# Hank2.net
KiCad netlist of a schematic drawn in EAGLE
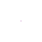
[diagram p0: schematic, sheet 1, part 1 of 2]
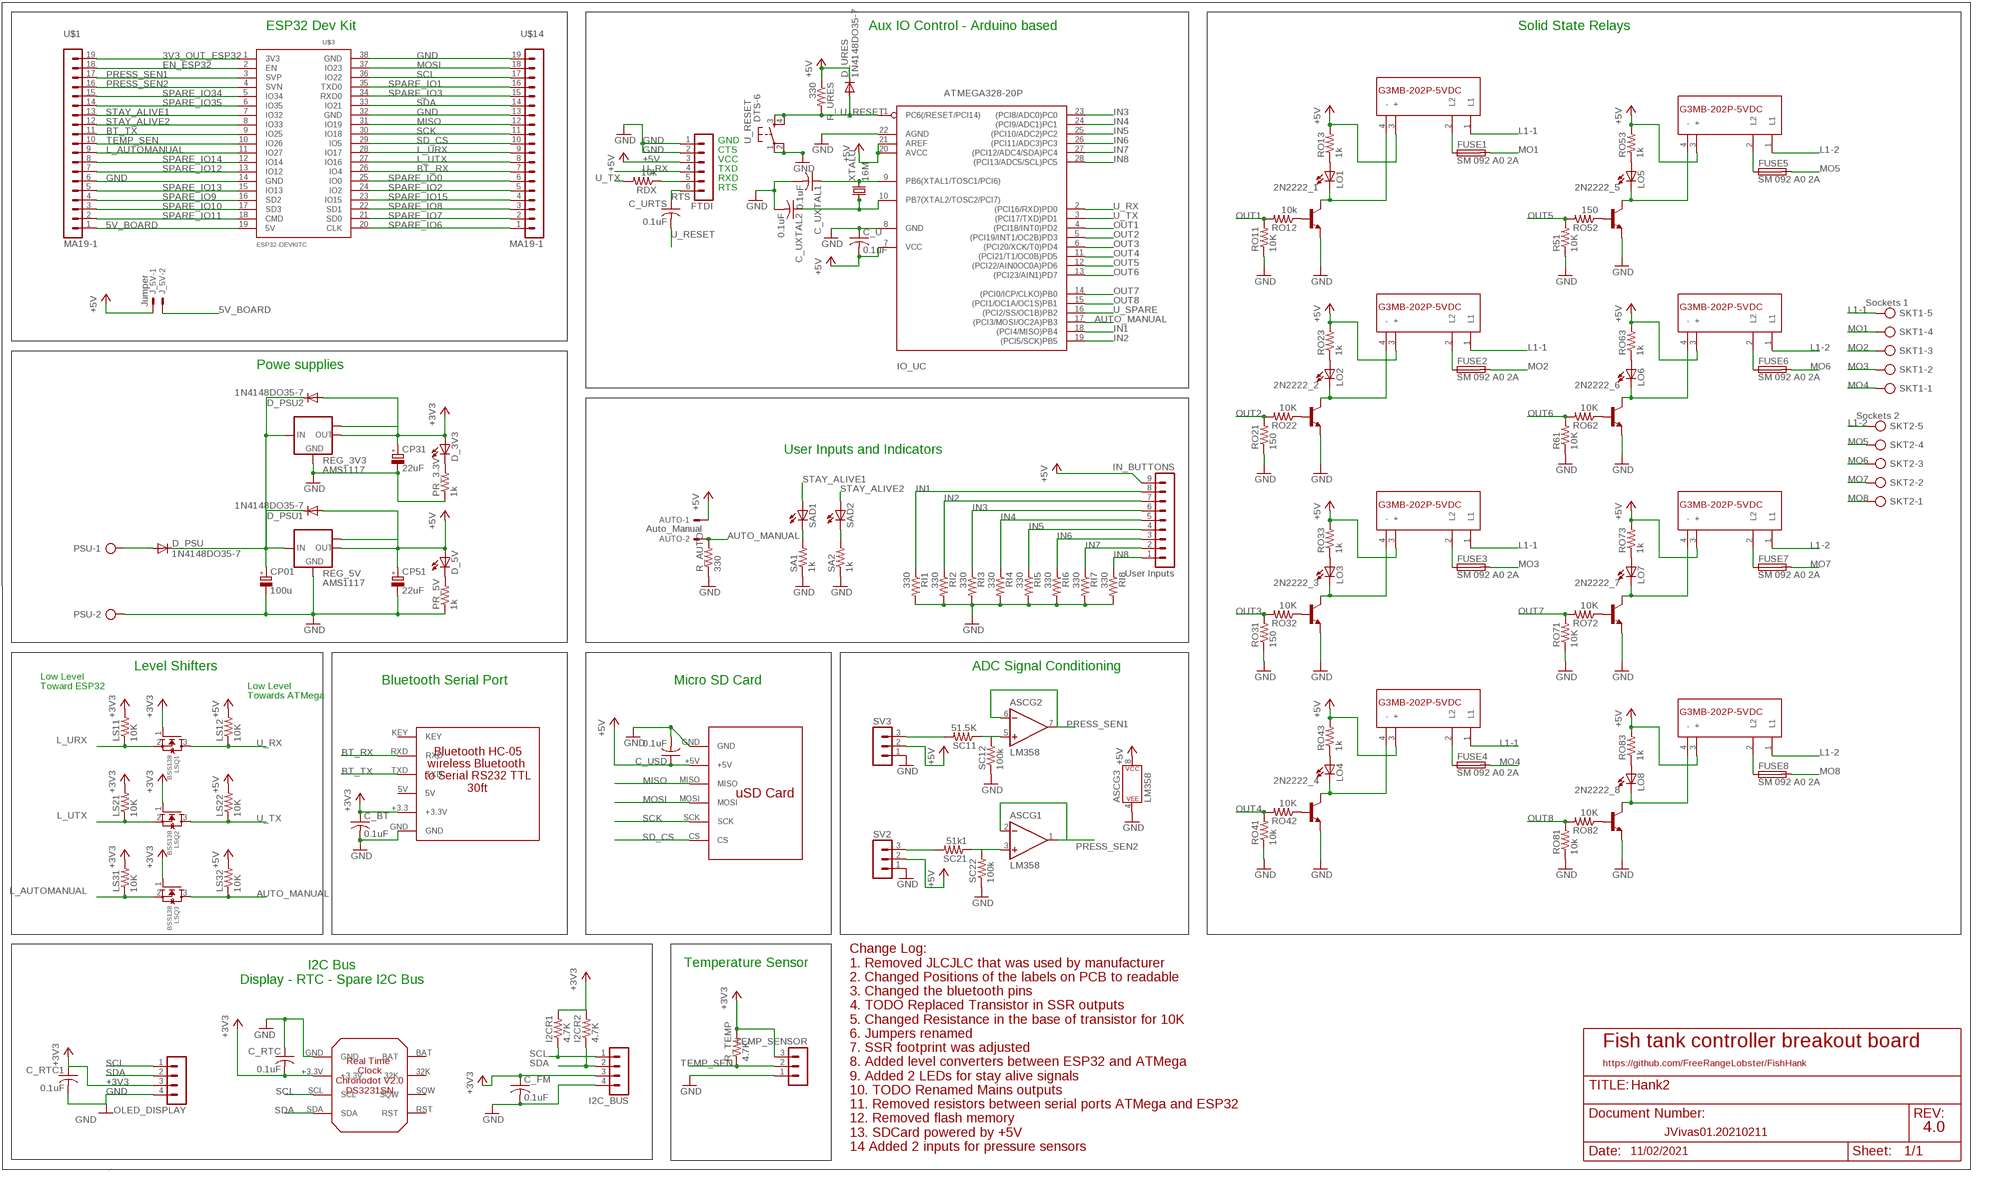
[diagram p1: schematic, sheet 1, part 2 of 2]

(export (version "E")
  (design (tool "Eeschema 10.0.6"))
  (components
    (comp (ref "2N2222_1")
      (value "-NPN-TO92-EBC")
      (footprint "eagle-import:TO92-EBC")
      (libsource (lib "eagle-import") (part "-NPN-TO92-EBC"))
    )
    (comp (ref "2N2222_2")
      (value "-NPN-TO92-EBC")
      (footprint "eagle-import:TO92-EBC")
      (libsource (lib "eagle-import") (part "-NPN-TO92-EBC"))
    )
    (comp (ref "2N2222_3")
      (value "-NPN-TO92-EBC")
      (footprint "eagle-import:TO92-EBC")
      (libsource (lib "eagle-import") (part "-NPN-TO92-EBC"))
    )
    (comp (ref "2N2222_4")
      (value "-NPN-TO92-EBC")
      (footprint "eagle-import:TO92-EBC")
      (libsource (lib "eagle-import") (part "-NPN-TO92-EBC"))
    )
    (comp (ref "2N2222_5")
      (value "-NPN-TO92-EBC")
      (footprint "eagle-import:TO92-EBC")
      (libsource (lib "eagle-import") (part "-NPN-TO92-EBC"))
    )
    (comp (ref "2N2222_6")
      (value "-NPN-TO92-EBC")
      (footprint "eagle-import:TO92-EBC")
      (libsource (lib "eagle-import") (part "-NPN-TO92-EBC"))
    )
    (comp (ref "2N2222_7")
      (value "-NPN-TO92-EBC")
      (footprint "eagle-import:TO92-EBC")
      (libsource (lib "eagle-import") (part "-NPN-TO92-EBC"))
    )
    (comp (ref "2N2222_8")
      (value "-NPN-TO92-EBC")
      (footprint "eagle-import:TO92-EBC")
      (libsource (lib "eagle-import") (part "-NPN-TO92-EBC"))
    )
    (comp (ref "ASC")
      (value "LM358")
      (footprint "eagle-import:DIP08")
      (libsource (lib "eagle-import") (part "LM358"))
    )
    (comp (ref "AUTO")
      (value "Auto_Manual")
      (footprint "eagle-import:22-23-2021")
      (fields (field (name "MF") "MOLEX") (field (name "MPN") "22-23-2021"))
      (libsource (lib "eagle-import") (part "22-23-2021"))
    )
    (comp (ref "CP01")
      (value "100u")
      (footprint "eagle-import:E2,5-6")
      (libsource (lib "eagle-import") (part "CPOL-EUE2.5-6"))
    )
    (comp (ref "CP31")
      (value "22uF")
      (footprint "eagle-import:E2,5-6")
      (libsource (lib "eagle-import") (part "CPOL-EUE2.5-6"))
    )
    (comp (ref "CP51")
      (value "22uF")
      (footprint "eagle-import:E2,5-6")
      (libsource (lib "eagle-import") (part "CPOL-EUE2.5-6"))
    )
    (comp (ref "C_BT")
      (value "0.1uF")
      (footprint "eagle-import:C025-024X044")
      (libsource (lib "eagle-import") (part "C-US025-024X044"))
    )
    (comp (ref "C_FM")
      (value "0.1uF")
      (footprint "eagle-import:C025-024X044")
      (libsource (lib "eagle-import") (part "C-US025-024X044"))
    )
    (comp (ref "C_RTC")
      (value "0.1uF")
      (footprint "eagle-import:C025-024X044")
      (libsource (lib "eagle-import") (part "C-US025-024X044"))
    )
    (comp (ref "C_RTC1")
      (value "0.1uF")
      (footprint "eagle-import:C025-024X044")
      (libsource (lib "eagle-import") (part "C-US025-024X044"))
    )
    (comp (ref "C_U")
      (value "0.1uF")
      (footprint "eagle-import:C025-024X044")
      (libsource (lib "eagle-import") (part "C-US025-024X044"))
    )
    (comp (ref "C_URTS")
      (value "0.1uF")
      (footprint "eagle-import:C025-024X044")
      (libsource (lib "eagle-import") (part "C-US025-024X044"))
    )
    (comp (ref "C_USD")
      (value "0.1uF")
      (footprint "eagle-import:C025-024X044")
      (libsource (lib "eagle-import") (part "C-US025-024X044"))
    )
    (comp (ref "C_UXTAL1")
      (value "0.1uF")
      (footprint "eagle-import:C025-024X044")
      (libsource (lib "eagle-import") (part "C-US025-024X044"))
    )
    (comp (ref "C_UXTAL2")
      (value "0.1uF")
      (footprint "eagle-import:C025-024X044")
      (libsource (lib "eagle-import") (part "C-US025-024X044"))
    )
    (comp (ref "D_3V3")
      (value "LED3MM")
      (footprint "eagle-import:LED3MM")
      (libsource (lib "eagle-import") (part "LED3MM"))
    )
    (comp (ref "D_5V")
      (value "LED3MM")
      (footprint "eagle-import:LED3MM")
      (libsource (lib "eagle-import") (part "LED3MM"))
    )
    (comp (ref "D_PSU")
      (value "1N4148DO35-7")
      (footprint "eagle-import:DO35-7")
      (libsource (lib "eagle-import") (part "1N4148DO35-7"))
    )
    (comp (ref "D_PSU1")
      (value "1N4148DO35-7")
      (footprint "eagle-import:DO35-7")
      (libsource (lib "eagle-import") (part "1N4148DO35-7"))
    )
    (comp (ref "D_PSU2")
      (value "1N4148DO35-7")
      (footprint "eagle-import:DO35-7")
      (libsource (lib "eagle-import") (part "1N4148DO35-7"))
    )
    (comp (ref "D_URES")
      (value "1N4148DO35-7")
      (footprint "eagle-import:DO35-7")
      (libsource (lib "eagle-import") (part "1N4148DO35-7"))
    )
    (comp (ref "FTDI")
      (value "MA06-1")
      (footprint "eagle-import:MA06-1")
      (libsource (lib "eagle-import") (part "MA06-1"))
    )
    (comp (ref "FUSE1")
      (value "SM 092 A0 2A")
      (footprint "eagle-import:PICOFUSE")
      (libsource (lib "eagle-import") (part "FUSEPICOFUSE"))
    )
    (comp (ref "FUSE2")
      (value "SM 092 A0 2A")
      (footprint "eagle-import:PICOFUSE")
      (libsource (lib "eagle-import") (part "FUSEPICOFUSE"))
    )
    (comp (ref "FUSE3")
      (value "SM 092 A0 2A")
      (footprint "eagle-import:PICOFUSE")
      (libsource (lib "eagle-import") (part "FUSEPICOFUSE"))
    )
    (comp (ref "FUSE4")
      (value "SM 092 A0 2A")
      (footprint "eagle-import:PICOFUSE")
      (libsource (lib "eagle-import") (part "FUSEPICOFUSE"))
    )
    (comp (ref "FUSE5")
      (value "SM 092 A0 2A")
      (footprint "eagle-import:PICOFUSE")
      (libsource (lib "eagle-import") (part "FUSEPICOFUSE"))
    )
    (comp (ref "FUSE6")
      (value "SM 092 A0 2A")
      (footprint "eagle-import:PICOFUSE")
      (libsource (lib "eagle-import") (part "FUSEPICOFUSE"))
    )
    (comp (ref "FUSE7")
      (value "SM 092 A0 2A")
      (footprint "eagle-import:PICOFUSE")
      (libsource (lib "eagle-import") (part "FUSEPICOFUSE"))
    )
    (comp (ref "FUSE8")
      (value "SM 092 A0 2A")
      (footprint "eagle-import:PICOFUSE")
      (libsource (lib "eagle-import") (part "FUSEPICOFUSE"))
    )
    (comp (ref "I2CR1")
      (value "4.7K")
      (footprint "eagle-import:0207_10")
      (libsource (lib "eagle-import") (part "R-US_0207/10"))
    )
    (comp (ref "I2CR2")
      (value "4.7K")
      (footprint "eagle-import:0207_10")
      (libsource (lib "eagle-import") (part "R-US_0207/10"))
    )
    (comp (ref "I2C_BUS")
      (value "MA04-1")
      (footprint "eagle-import:MA04-1")
      (libsource (lib "eagle-import") (part "MA04-1"))
    )
    (comp (ref "IN_BUTTONS")
      (value "User Inputs")
      (footprint "eagle-import:MA09-1")
      (libsource (lib "eagle-import") (part "MA09-1"))
    )
    (comp (ref "IO_UC")
      (value "ATMEGA328-20P")
      (footprint "eagle-import:DIL28-3")
      (libsource (lib "eagle-import") (part "ATMEGA328P-20"))
    )
    (comp (ref "J_5V")
      (value "Jumper")
      (footprint "eagle-import:22-23-2021")
      (fields (field (name "MF") "MOLEX") (field (name "MPN") "22-23-2021"))
      (libsource (lib "eagle-import") (part "22-23-2021"))
    )
    (comp (ref "LO1")
      (value "LED3MM")
      (footprint "eagle-import:LED3MM")
      (libsource (lib "eagle-import") (part "LED3MM"))
    )
    (comp (ref "LO2")
      (value "LED3MM")
      (footprint "eagle-import:LED3MM")
      (libsource (lib "eagle-import") (part "LED3MM"))
    )
    (comp (ref "LO3")
      (value "LED3MM")
      (footprint "eagle-import:LED3MM")
      (libsource (lib "eagle-import") (part "LED3MM"))
    )
    (comp (ref "LO4")
      (value "LED3MM")
      (footprint "eagle-import:LED3MM")
      (libsource (lib "eagle-import") (part "LED3MM"))
    )
    (comp (ref "LO5")
      (value "LED3MM")
      (footprint "eagle-import:LED3MM")
      (libsource (lib "eagle-import") (part "LED3MM"))
    )
    (comp (ref "LO6")
      (value "LED3MM")
      (footprint "eagle-import:LED3MM")
      (libsource (lib "eagle-import") (part "LED3MM"))
    )
    (comp (ref "LO7")
      (value "LED3MM")
      (footprint "eagle-import:LED3MM")
      (libsource (lib "eagle-import") (part "LED3MM"))
    )
    (comp (ref "LO8")
      (value "LED3MM")
      (footprint "eagle-import:LED3MM")
      (libsource (lib "eagle-import") (part "LED3MM"))
    )
    (comp (ref "LS11")
      (value "10K")
      (footprint "eagle-import:0207_10")
      (libsource (lib "eagle-import") (part "R-US_0207/10"))
    )
    (comp (ref "LS12")
      (value "10K")
      (footprint "eagle-import:0207_10")
      (libsource (lib "eagle-import") (part "R-US_0207/10"))
    )
    (comp (ref "LS21")
      (value "10K")
      (footprint "eagle-import:0207_10")
      (libsource (lib "eagle-import") (part "R-US_0207/10"))
    )
    (comp (ref "LS22")
      (value "10K")
      (footprint "eagle-import:0207_10")
      (libsource (lib "eagle-import") (part "R-US_0207/10"))
    )
    (comp (ref "LS31")
      (value "10K")
      (footprint "eagle-import:0207_10")
      (libsource (lib "eagle-import") (part "R-US_0207/10"))
    )
    (comp (ref "LS32")
      (value "10K")
      (footprint "eagle-import:0207_10")
      (libsource (lib "eagle-import") (part "R-US_0207/10"))
    )
    (comp (ref "LSQ1")
      (value "BSS138")
      (footprint "eagle-import:SOT23")
      (libsource (lib "eagle-import") (part "MOSFET-NREFLOW"))
    )
    (comp (ref "LSQ2")
      (value "BSS138")
      (footprint "eagle-import:SOT23")
      (libsource (lib "eagle-import") (part "MOSFET-NREFLOW"))
    )
    (comp (ref "LSQ3")
      (value "BSS138")
      (footprint "eagle-import:SOT23")
      (libsource (lib "eagle-import") (part "MOSFET-NREFLOW"))
    )
    (comp (ref "OLED_DISPLAY")
      (value "MA04-1")
      (footprint "eagle-import:MA04-1")
      (libsource (lib "eagle-import") (part "MA04-1"))
    )
    (comp (ref "PR_3.3V")
      (value "1k")
      (footprint "eagle-import:0207_10")
      (libsource (lib "eagle-import") (part "R-US_0207/10"))
    )
    (comp (ref "PR_5V")
      (value "1k")
      (footprint "eagle-import:0207_10")
      (libsource (lib "eagle-import") (part "R-US_0207/10"))
    )
    (comp (ref "PSU")
      (value "AK500/2")
      (footprint "eagle-import:AK500_2")
      (libsource (lib "eagle-import") (part "AK500/2"))
    )
    (comp (ref "R51")
      (value "10K")
      (footprint "eagle-import:0207_10")
      (libsource (lib "eagle-import") (part "R-US_0207/10"))
    )
    (comp (ref "R61")
      (value "10K")
      (footprint "eagle-import:0207_10")
      (libsource (lib "eagle-import") (part "R-US_0207/10"))
    )
    (comp (ref "RDX")
      (value "10k")
      (footprint "eagle-import:0207_10")
      (libsource (lib "eagle-import") (part "R-US_0207/10"))
    )
    (comp (ref "REG_3V3")
      (value "AMS1117")
      (footprint "eagle-import:SOT223")
      (libsource (lib "eagle-import") (part "AMS1117"))
    )
    (comp (ref "REG_5V")
      (value "AMS1117")
      (footprint "eagle-import:SOT223")
      (libsource (lib "eagle-import") (part "AMS1117"))
    )
    (comp (ref "RI1")
      (value "330")
      (footprint "eagle-import:0207_10")
      (libsource (lib "eagle-import") (part "R-US_0207/10"))
    )
    (comp (ref "RI2")
      (value "330")
      (footprint "eagle-import:0207_10")
      (libsource (lib "eagle-import") (part "R-US_0207/10"))
    )
    (comp (ref "RI3")
      (value "330")
      (footprint "eagle-import:0207_10")
      (libsource (lib "eagle-import") (part "R-US_0207/10"))
    )
    (comp (ref "RI4")
      (value "330")
      (footprint "eagle-import:0207_10")
      (libsource (lib "eagle-import") (part "R-US_0207/10"))
    )
    (comp (ref "RI5")
      (value "330")
      (footprint "eagle-import:0207_10")
      (libsource (lib "eagle-import") (part "R-US_0207/10"))
    )
    (comp (ref "RI6")
      (value "330")
      (footprint "eagle-import:0207_10")
      (libsource (lib "eagle-import") (part "R-US_0207/10"))
    )
    (comp (ref "RI7")
      (value "330")
      (footprint "eagle-import:0207_10")
      (libsource (lib "eagle-import") (part "R-US_0207/10"))
    )
    (comp (ref "RI8")
      (value "330")
      (footprint "eagle-import:0207_10")
      (libsource (lib "eagle-import") (part "R-US_0207/10"))
    )
    (comp (ref "RO11")
      (value "10K")
      (footprint "eagle-import:0207_10")
      (libsource (lib "eagle-import") (part "R-US_0207/10"))
    )
    (comp (ref "RO12")
      (value "10k")
      (footprint "eagle-import:0207_10")
      (libsource (lib "eagle-import") (part "R-US_0207/10"))
    )
    (comp (ref "RO13")
      (value "1k")
      (footprint "eagle-import:0207_10")
      (libsource (lib "eagle-import") (part "R-US_0207/10"))
    )
    (comp (ref "RO21")
      (value "150")
      (footprint "eagle-import:0207_10")
      (libsource (lib "eagle-import") (part "R-US_0207/10"))
    )
    (comp (ref "RO22")
      (value "10K")
      (footprint "eagle-import:0207_10")
      (libsource (lib "eagle-import") (part "R-US_0207/10"))
    )
    (comp (ref "RO23")
      (value "1k")
      (footprint "eagle-import:0207_10")
      (libsource (lib "eagle-import") (part "R-US_0207/10"))
    )
    (comp (ref "RO31")
      (value "150")
      (footprint "eagle-import:0207_10")
      (libsource (lib "eagle-import") (part "R-US_0207/10"))
    )
    (comp (ref "RO32")
      (value "10K")
      (footprint "eagle-import:0207_10")
      (libsource (lib "eagle-import") (part "R-US_0207/10"))
    )
    (comp (ref "RO33")
      (value "1k")
      (footprint "eagle-import:0207_10")
      (libsource (lib "eagle-import") (part "R-US_0207/10"))
    )
    (comp (ref "RO41")
      (value "10k")
      (footprint "eagle-import:0207_10")
      (libsource (lib "eagle-import") (part "R-US_0207/10"))
    )
    (comp (ref "RO42")
      (value "10K")
      (footprint "eagle-import:0207_10")
      (libsource (lib "eagle-import") (part "R-US_0207/10"))
    )
    (comp (ref "RO43")
      (value "1k")
      (footprint "eagle-import:0207_10")
      (libsource (lib "eagle-import") (part "R-US_0207/10"))
    )
    (comp (ref "RO52")
      (value "150")
      (footprint "eagle-import:0207_10")
      (libsource (lib "eagle-import") (part "R-US_0207/10"))
    )
    (comp (ref "RO53")
      (value "1k")
      (footprint "eagle-import:0207_10")
      (libsource (lib "eagle-import") (part "R-US_0207/10"))
    )
    (comp (ref "RO62")
      (value "10K")
      (footprint "eagle-import:0207_10")
      (libsource (lib "eagle-import") (part "R-US_0207/10"))
    )
    (comp (ref "RO63")
      (value "1k")
      (footprint "eagle-import:0207_10")
      (libsource (lib "eagle-import") (part "R-US_0207/10"))
    )
    (comp (ref "RO71")
      (value "10K")
      (footprint "eagle-import:0207_10")
      (libsource (lib "eagle-import") (part "R-US_0207/10"))
    )
    (comp (ref "RO72")
      (value "10K")
      (footprint "eagle-import:0207_10")
      (libsource (lib "eagle-import") (part "R-US_0207/10"))
    )
    (comp (ref "RO73")
      (value "1k")
      (footprint "eagle-import:0207_10")
      (libsource (lib "eagle-import") (part "R-US_0207/10"))
    )
    (comp (ref "RO81")
      (value "10k")
      (footprint "eagle-import:0207_10")
      (libsource (lib "eagle-import") (part "R-US_0207/10"))
    )
    (comp (ref "RO82")
      (value "10K")
      (footprint "eagle-import:0207_10")
      (libsource (lib "eagle-import") (part "R-US_0207/10"))
    )
    (comp (ref "RO83")
      (value "1k")
      (footprint "eagle-import:0207_10")
      (libsource (lib "eagle-import") (part "R-US_0207/10"))
    )
    (comp (ref "R_AUTO")
      (value "330")
      (footprint "eagle-import:0207_10")
      (libsource (lib "eagle-import") (part "R-US_0207/10"))
    )
    (comp (ref "R_TEMP")
      (value "4.7K")
      (footprint "eagle-import:0207_10")
      (libsource (lib "eagle-import") (part "R-US_0207/10"))
    )
    (comp (ref "R_URES")
      (value "330")
      (footprint "eagle-import:0207_10")
      (libsource (lib "eagle-import") (part "R-US_0207/10"))
    )
    (comp (ref "SA1")
      (value "1k")
      (footprint "eagle-import:0207_10")
      (libsource (lib "eagle-import") (part "R-US_0207/10"))
    )
    (comp (ref "SA2")
      (value "1k")
      (footprint "eagle-import:0207_10")
      (libsource (lib "eagle-import") (part "R-US_0207/10"))
    )
    (comp (ref "SAD1")
      (value "LED3MM")
      (footprint "eagle-import:LED3MM")
      (libsource (lib "eagle-import") (part "LED3MM"))
    )
    (comp (ref "SAD2")
      (value "LED3MM")
      (footprint "eagle-import:LED3MM")
      (libsource (lib "eagle-import") (part "LED3MM"))
    )
    (comp (ref "SC11")
      (value "51.5K")
      (footprint "eagle-import:0207_10")
      (libsource (lib "eagle-import") (part "R-US_0207/10"))
    )
    (comp (ref "SC12")
      (value "100k")
      (footprint "eagle-import:0207_10")
      (libsource (lib "eagle-import") (part "R-US_0207/10"))
    )
    (comp (ref "SC21")
      (value "51k1")
      (footprint "eagle-import:0207_10")
      (libsource (lib "eagle-import") (part "R-US_0207/10"))
    )
    (comp (ref "SC22")
      (value "100k")
      (footprint "eagle-import:0207_10")
      (libsource (lib "eagle-import") (part "R-US_0207/10"))
    )
    (comp (ref "SKT1")
      (value "Sockets 1")
      (footprint "eagle-import:AK500_5")
      (libsource (lib "eagle-import") (part "AK500/5"))
    )
    (comp (ref "SKT2")
      (value "Sockets 2")
      (footprint "eagle-import:AK500_5")
      (libsource (lib "eagle-import") (part "AK500/5"))
    )
    (comp (ref "SV2")
      (value "MA03-1")
      (footprint "eagle-import:MA03-1")
      (libsource (lib "eagle-import") (part "MA03-1"))
    )
    (comp (ref "SV3")
      (value "MA03-1")
      (footprint "eagle-import:MA03-1")
      (libsource (lib "eagle-import") (part "MA03-1"))
    )
    (comp (ref "TEMP_SENSOR")
      (value "MA03-1")
      (footprint "eagle-import:MA03-1")
      (libsource (lib "eagle-import") (part "MA03-1"))
    )
    (comp (ref "U$1")
      (value "MA19-1")
      (footprint "eagle-import:MA19-1")
      (libsource (lib "eagle-import") (part "MA19-1"))
    )
    (comp (ref "U$2")
      (value "BLUETOOTH")
      (footprint "eagle-import:BLUETOOTH_FOOTPRINT")
      (libsource (lib "eagle-import") (part "BLUETOOTH"))
    )
    (comp (ref "U$3")
      (value "ESP32DEVKITC")
      (footprint "eagle-import:ESP32-DEVKITC")
      (libsource (lib "eagle-import") (part "ESP32DEVKITC"))
    )
    (comp (ref "U$4")
      (value "SSR")
      (footprint "eagle-import:SSR_FOOTPRINT")
      (libsource (lib "eagle-import") (part "SSR"))
    )
    (comp (ref "U$5")
      (value "SSR")
      (footprint "eagle-import:SSR_FOOTPRINT")
      (libsource (lib "eagle-import") (part "SSR"))
    )
    (comp (ref "U$6")
      (value "RTC")
      (footprint "eagle-import:RTC_FOOTPRINT")
      (libsource (lib "eagle-import") (part "RTC"))
    )
    (comp (ref "U$8")
      (value "SSR")
      (footprint "eagle-import:SSR_FOOTPRINT")
      (libsource (lib "eagle-import") (part "SSR"))
    )
    (comp (ref "U$9")
      (value "SSR")
      (footprint "eagle-import:SSR_FOOTPRINT")
      (libsource (lib "eagle-import") (part "SSR"))
    )
    (comp (ref "U$10")
      (value "SSR")
      (footprint "eagle-import:SSR_FOOTPRINT")
      (libsource (lib "eagle-import") (part "SSR"))
    )
    (comp (ref "U$11")
      (value "SSR")
      (footprint "eagle-import:SSR_FOOTPRINT")
      (libsource (lib "eagle-import") (part "SSR"))
    )
    (comp (ref "U$12")
      (value "SSR")
      (footprint "eagle-import:SSR_FOOTPRINT")
      (libsource (lib "eagle-import") (part "SSR"))
    )
    (comp (ref "U$13")
      (value "SSR")
      (footprint "eagle-import:SSR_FOOTPRINT")
      (libsource (lib "eagle-import") (part "SSR"))
    )
    (comp (ref "U$14")
      (value "MA19-1")
      (footprint "eagle-import:MA19-1")
      (libsource (lib "eagle-import") (part "MA19-1"))
    )
    (comp (ref "U$15")
      (value "SD_CARD_READER")
      (footprint "eagle-import:SD_CARD_READER_FOOTPRINT")
      (libsource (lib "eagle-import") (part "SD_CARD_READER"))
    )
    (comp (ref "U_RESET")
      (value "DTS-6")
      (footprint "eagle-import:DTS-6")
      (libsource (lib "eagle-import") (part "DTS-6"))
    )
    (comp (ref "XTALU")
      (value "16M")
      (footprint "eagle-import:HC49_S")
      (libsource (lib "eagle-import") (part "CRYSTALHC49S"))
    )
  )
  (nets
    (net (code "1") (name "+3V3") (class "Default")
      (node (ref "CP31") (pin "+") (pinfunction "+_+") (pintype "passive"))
      (node (ref "C_BT") (pin "1") (pinfunction "1_1") (pintype "passive"))
      (node (ref "C_FM") (pin "1") (pinfunction "1_1") (pintype "passive"))
      (node (ref "C_RTC") (pin "2") (pinfunction "2_2") (pintype "passive"))
      (node (ref "C_RTC1") (pin "1") (pinfunction "1_1") (pintype "passive"))
      (node (ref "D_3V3") (pin "A") (pinfunction "A_A") (pintype "passive"))
      (node (ref "D_PSU2") (pin "A") (pinfunction "A_A") (pintype "passive"))
      (node (ref "I2CR1") (pin "2") (pinfunction "2_2") (pintype "passive"))
      (node (ref "I2CR2") (pin "2") (pinfunction "2_2") (pintype "passive"))
      (node (ref "I2C_BUS") (pin "3") (pinfunction "3_3") (pintype "passive"))
      (node (ref "LS11") (pin "2") (pinfunction "2_2") (pintype "passive"))
      (node (ref "LS21") (pin "2") (pinfunction "2_2") (pintype "passive"))
      (node (ref "LS31") (pin "2") (pinfunction "2_2") (pintype "passive"))
      (node (ref "LSQ1") (pin "1") (pinfunction "G_1") (pintype "bidirectional"))
      (node (ref "LSQ2") (pin "1") (pinfunction "G_1") (pintype "bidirectional"))
      (node (ref "LSQ3") (pin "1") (pinfunction "G_1") (pintype "bidirectional"))
      (node (ref "OLED_DISPLAY") (pin "3") (pinfunction "3_3") (pintype "passive"))
      (node (ref "REG_3V3") (pin "2") (pinfunction "OUT_2") (pintype "passive"))
      (node (ref "REG_3V3") (pin "TAB") (pinfunction "OUT1_TAB") (pintype "passive"))
      (node (ref "R_TEMP") (pin "2") (pinfunction "2_2") (pintype "passive"))
      (node (ref "TEMP_SENSOR") (pin "3") (pinfunction "3_3") (pintype "passive"))
      (node (ref "U$2") (pin "+3.3") (pinfunction "+3.3V_+3.3") (pintype "bidirectional"))
      (node (ref "U$6") (pin "+3.3V") (pinfunction "+3.3V_+3.3V") (pintype "bidirectional"))
    )
    (net (code "2") (name "+5V") (class "Default")
      (node (ref "ASC") (pin "8") (pinfunction "P$V+_8") (pintype "bidirectional"))
      (node (ref "AUTO") (pin "1") (pinfunction "S_1") (pintype "passive"))
      (node (ref "CP51") (pin "+") (pinfunction "+_+") (pintype "passive"))
      (node (ref "C_U") (pin "2") (pinfunction "2_2") (pintype "passive"))
      (node (ref "C_USD") (pin "1") (pinfunction "1_1") (pintype "passive"))
      (node (ref "D_5V") (pin "A") (pinfunction "A_A") (pintype "passive"))
      (node (ref "D_PSU1") (pin "A") (pinfunction "A_A") (pintype "passive"))
      (node (ref "D_URES") (pin "C") (pinfunction "C_C") (pintype "passive"))
      (node (ref "FTDI") (pin "3") (pinfunction "3_3") (pintype "passive"))
      (node (ref "IN_BUTTONS") (pin "9") (pinfunction "9_9") (pintype "passive"))
      (node (ref "IO_UC") (pin "20") (pinfunction "AVCC_20") (pintype "bidirectional"))
      (node (ref "IO_UC") (pin "21") (pinfunction "AREF_21") (pintype "bidirectional"))
      (node (ref "IO_UC") (pin "7") (pinfunction "VCC_7") (pintype "bidirectional"))
      (node (ref "J_5V") (pin "1") (pinfunction "S_1") (pintype "passive"))
      (node (ref "LS12") (pin "2") (pinfunction "2_2") (pintype "passive"))
      (node (ref "LS22") (pin "2") (pinfunction "2_2") (pintype "passive"))
      (node (ref "LS32") (pin "2") (pinfunction "2_2") (pintype "passive"))
      (node (ref "REG_5V") (pin "2") (pinfunction "OUT_2") (pintype "passive"))
      (node (ref "REG_5V") (pin "TAB") (pinfunction "OUT1_TAB") (pintype "passive"))
      (node (ref "RO13") (pin "2") (pinfunction "2_2") (pintype "passive"))
      (node (ref "RO23") (pin "2") (pinfunction "2_2") (pintype "passive"))
      (node (ref "RO33") (pin "2") (pinfunction "2_2") (pintype "passive"))
      (node (ref "RO43") (pin "2") (pinfunction "2_2") (pintype "passive"))
      (node (ref "RO53") (pin "2") (pinfunction "2_2") (pintype "passive"))
      (node (ref "RO63") (pin "2") (pinfunction "2_2") (pintype "passive"))
      (node (ref "RO73") (pin "2") (pinfunction "2_2") (pintype "passive"))
      (node (ref "RO83") (pin "2") (pinfunction "2_2") (pintype "passive"))
      (node (ref "R_URES") (pin "1") (pinfunction "1_1") (pintype "passive"))
      (node (ref "SV2") (pin "2") (pinfunction "2_2") (pintype "passive"))
      (node (ref "SV3") (pin "2") (pinfunction "2_2") (pintype "passive"))
      (node (ref "U$10") (pin "3") (pinfunction "+_3") (pintype "bidirectional"))
      (node (ref "U$11") (pin "3") (pinfunction "+_3") (pintype "bidirectional"))
      (node (ref "U$12") (pin "3") (pinfunction "+_3") (pintype "bidirectional"))
      (node (ref "U$13") (pin "3") (pinfunction "+_3") (pintype "bidirectional"))
      (node (ref "U$15") (pin "+5V") (pinfunction "+5V_+5V") (pintype "bidirectional"))
      (node (ref "U$4") (pin "3") (pinfunction "+_3") (pintype "bidirectional"))
      (node (ref "U$5") (pin "3") (pinfunction "+_3") (pintype "bidirectional"))
      (node (ref "U$8") (pin "3") (pinfunction "+_3") (pintype "bidirectional"))
      (node (ref "U$9") (pin "3") (pinfunction "+_3") (pintype "bidirectional"))
    )
    (net (code "3") (name "/3V3_OUT_ESP32") (class "Default")
      (node (ref "U$1") (pin "19") (pinfunction "19_19") (pintype "passive"))
      (node (ref "U$3") (pin "1") (pinfunction "3V3_1") (pintype "bidirectional"))
    )
    (net (code "4") (name "/5V_BOARD") (class "Default")
      (node (ref "J_5V") (pin "2") (pinfunction "S_2") (pintype "passive"))
      (node (ref "U$1") (pin "1") (pinfunction "1_1") (pintype "passive"))
      (node (ref "U$3") (pin "19") (pinfunction "5V_19") (pintype "bidirectional"))
    )
    (net (code "5") (name "/AUTO_MANUAL") (class "Default")
      (node (ref "AUTO") (pin "2") (pinfunction "S_2") (pintype "passive"))
      (node (ref "IO_UC") (pin "17") (pinfunction "(PCI3/MOSI/OC2A)PB3_17") (pintype "bidirectional"))
      (node (ref "LS32") (pin "1") (pinfunction "1_1") (pintype "passive"))
      (node (ref "LSQ3") (pin "3") (pinfunction "D_3") (pintype "bidirectional"))
      (node (ref "R_AUTO") (pin "2") (pinfunction "2_2") (pintype "passive"))
    )
    (net (code "6") (name "/BT_RX") (class "Default")
      (node (ref "U$14") (pin "7") (pinfunction "7_7") (pintype "passive"))
      (node (ref "U$2") (pin "RXD") (pinfunction "RXD_RXD") (pintype "bidirectional"))
      (node (ref "U$3") (pin "26") (pinfunction "IO4_26") (pintype "bidirectional"))
    )
    (net (code "7") (name "/BT_TX") (class "Default")
      (node (ref "U$1") (pin "11") (pinfunction "11_11") (pintype "passive"))
      (node (ref "U$2") (pin "TXD") (pinfunction "TXD_TXD") (pintype "bidirectional"))
      (node (ref "U$3") (pin "9") (pinfunction "IO25_9") (pintype "bidirectional"))
    )
    (net (code "8") (name "/EN_ESP32") (class "Default")
      (node (ref "U$1") (pin "18") (pinfunction "18_18") (pintype "passive"))
      (node (ref "U$3") (pin "2") (pinfunction "EN_2") (pintype "bidirectional"))
    )
    (net (code "9") (name "/IN1") (class "Default")
      (node (ref "IN_BUTTONS") (pin "8") (pinfunction "8_8") (pintype "passive"))
      (node (ref "IO_UC") (pin "18") (pinfunction "(PCI4/MISO)PB4_18") (pintype "bidirectional"))
      (node (ref "RI1") (pin "1") (pinfunction "1_1") (pintype "passive"))
    )
    (net (code "10") (name "/IN2") (class "Default")
      (node (ref "IN_BUTTONS") (pin "7") (pinfunction "7_7") (pintype "passive"))
      (node (ref "IO_UC") (pin "19") (pinfunction "(PCI5/SCK)PB5_19") (pintype "bidirectional"))
      (node (ref "RI2") (pin "1") (pinfunction "1_1") (pintype "passive"))
    )
    (net (code "11") (name "/IN3") (class "Default")
      (node (ref "IN_BUTTONS") (pin "6") (pinfunction "6_6") (pintype "passive"))
      (node (ref "IO_UC") (pin "23") (pinfunction "(PCI8/ADC0)PC0_23") (pintype "bidirectional"))
      (node (ref "RI3") (pin "1") (pinfunction "1_1") (pintype "passive"))
    )
    (net (code "12") (name "/IN4") (class "Default")
      (node (ref "IN_BUTTONS") (pin "5") (pinfunction "5_5") (pintype "passive"))
      (node (ref "IO_UC") (pin "24") (pinfunction "(PCI9/ADC1)PC1_24") (pintype "bidirectional"))
      (node (ref "RI4") (pin "1") (pinfunction "1_1") (pintype "passive"))
    )
    (net (code "13") (name "/IN5") (class "Default")
      (node (ref "IN_BUTTONS") (pin "4") (pinfunction "4_4") (pintype "passive"))
      (node (ref "IO_UC") (pin "25") (pinfunction "(PCI10/ADC2)PC2_25") (pintype "bidirectional"))
      (node (ref "RI5") (pin "1") (pinfunction "1_1") (pintype "passive"))
    )
    (net (code "14") (name "/IN6") (class "Default")
      (node (ref "IN_BUTTONS") (pin "3") (pinfunction "3_3") (pintype "passive"))
      (node (ref "IO_UC") (pin "26") (pinfunction "(PCI11/ADC3)PC3_26") (pintype "bidirectional"))
      (node (ref "RI6") (pin "1") (pinfunction "1_1") (pintype "passive"))
    )
    (net (code "15") (name "/IN7") (class "Default")
      (node (ref "IN_BUTTONS") (pin "2") (pinfunction "2_2") (pintype "passive"))
      (node (ref "IO_UC") (pin "27") (pinfunction "(PCI12/ADC4/SDA)PC4_27") (pintype "bidirectional"))
      (node (ref "RI7") (pin "1") (pinfunction "1_1") (pintype "passive"))
    )
    (net (code "16") (name "/IN8") (class "Default")
      (node (ref "IN_BUTTONS") (pin "1") (pinfunction "1_1") (pintype "passive"))
      (node (ref "IO_UC") (pin "28") (pinfunction "(PCI13/ADC5/SCL)PC5_28") (pintype "bidirectional"))
      (node (ref "RI8") (pin "1") (pinfunction "1_1") (pintype "passive"))
    )
    (net (code "17") (name "/L1-1") (class "Default")
      (node (ref "SKT1") (pin "5") (pinfunction "KL_5") (pintype "passive"))
      (node (ref "U$10") (pin "1") (pinfunction "L1_1") (pintype "bidirectional"))
      (node (ref "U$4") (pin "1") (pinfunction "L1_1") (pintype "bidirectional"))
      (node (ref "U$5") (pin "1") (pinfunction "L1_1") (pintype "bidirectional"))
      (node (ref "U$8") (pin "1") (pinfunction "L1_1") (pintype "bidirectional"))
    )
    (net (code "18") (name "/L1-2") (class "Default")
      (node (ref "SKT2") (pin "5") (pinfunction "KL_5") (pintype "passive"))
      (node (ref "U$11") (pin "1") (pinfunction "L1_1") (pintype "bidirectional"))
      (node (ref "U$12") (pin "1") (pinfunction "L1_1") (pintype "bidirectional"))
      (node (ref "U$13") (pin "1") (pinfunction "L1_1") (pintype "bidirectional"))
      (node (ref "U$9") (pin "1") (pinfunction "L1_1") (pintype "bidirectional"))
    )
    (net (code "19") (name "/L_AUTOMANUAL") (class "Default")
      (node (ref "LS31") (pin "1") (pinfunction "1_1") (pintype "passive"))
      (node (ref "LSQ3") (pin "2") (pinfunction "S_2") (pintype "bidirectional"))
      (node (ref "U$1") (pin "9") (pinfunction "9_9") (pintype "passive"))
      (node (ref "U$3") (pin "11") (pinfunction "IO27_11") (pintype "bidirectional"))
    )
    (net (code "20") (name "/L_URX") (class "Default")
      (node (ref "LS11") (pin "1") (pinfunction "1_1") (pintype "passive"))
      (node (ref "LSQ1") (pin "2") (pinfunction "S_2") (pintype "bidirectional"))
      (node (ref "U$14") (pin "9") (pinfunction "9_9") (pintype "passive"))
      (node (ref "U$3") (pin "28") (pinfunction "IO17_28") (pintype "bidirectional"))
    )
    (net (code "21") (name "/L_UTX") (class "Default")
      (node (ref "LS21") (pin "1") (pinfunction "1_1") (pintype "passive"))
      (node (ref "LSQ2") (pin "2") (pinfunction "S_2") (pintype "bidirectional"))
      (node (ref "U$14") (pin "8") (pinfunction "8_8") (pintype "passive"))
      (node (ref "U$3") (pin "27") (pinfunction "IO16_27") (pintype "bidirectional"))
    )
    (net (code "22") (name "/MISO") (class "Default")
      (node (ref "U$14") (pin "12") (pinfunction "12_12") (pintype "passive"))
      (node (ref "U$15") (pin "MISO") (pinfunction "MISO_MISO") (pintype "bidirectional"))
      (node (ref "U$3") (pin "31") (pinfunction "IO19_31") (pintype "bidirectional"))
    )
    (net (code "23") (name "/MO1") (class "Default")
      (node (ref "FUSE1") (pin "2") (pinfunction "2_2") (pintype "passive"))
      (node (ref "SKT1") (pin "4") (pinfunction "KL_4") (pintype "passive"))
    )
    (net (code "24") (name "/MO2") (class "Default")
      (node (ref "FUSE2") (pin "2") (pinfunction "2_2") (pintype "passive"))
      (node (ref "SKT1") (pin "3") (pinfunction "KL_3") (pintype "passive"))
    )
    (net (code "25") (name "/MO3") (class "Default")
      (node (ref "FUSE3") (pin "2") (pinfunction "2_2") (pintype "passive"))
      (node (ref "SKT1") (pin "2") (pinfunction "KL_2") (pintype "passive"))
    )
    (net (code "26") (name "/MO4") (class "Default")
      (node (ref "FUSE4") (pin "2") (pinfunction "2_2") (pintype "passive"))
      (node (ref "SKT1") (pin "1") (pinfunction "KL_1") (pintype "passive"))
    )
    (net (code "27") (name "/MO5") (class "Default")
      (node (ref "FUSE5") (pin "2") (pinfunction "2_2") (pintype "passive"))
      (node (ref "SKT2") (pin "4") (pinfunction "KL_4") (pintype "passive"))
    )
    (net (code "28") (name "/MO6") (class "Default")
      (node (ref "FUSE6") (pin "2") (pinfunction "2_2") (pintype "passive"))
      (node (ref "SKT2") (pin "3") (pinfunction "KL_3") (pintype "passive"))
    )
    (net (code "29") (name "/MO7") (class "Default")
      (node (ref "FUSE7") (pin "2") (pinfunction "2_2") (pintype "passive"))
      (node (ref "SKT2") (pin "2") (pinfunction "KL_2") (pintype "passive"))
    )
    (net (code "30") (name "/MO8") (class "Default")
      (node (ref "FUSE8") (pin "2") (pinfunction "2_2") (pintype "passive"))
      (node (ref "SKT2") (pin "1") (pinfunction "KL_1") (pintype "passive"))
    )
    (net (code "31") (name "/MOSI") (class "Default")
      (node (ref "U$14") (pin "18") (pinfunction "18_18") (pintype "passive"))
      (node (ref "U$15") (pin "MOSI") (pinfunction "MOSI_MOSI") (pintype "bidirectional"))
      (node (ref "U$3") (pin "37") (pinfunction "IO23_37") (pintype "bidirectional"))
    )
    (net (code "32") (name "/OUT1") (class "Default")
      (node (ref "IO_UC") (pin "4") (pinfunction "(PCI18/INT0)PD2_4") (pintype "bidirectional"))
      (node (ref "RO11") (pin "2") (pinfunction "2_2") (pintype "passive"))
      (node (ref "RO12") (pin "2") (pinfunction "2_2") (pintype "passive"))
    )
    (net (code "33") (name "/OUT2") (class "Default")
      (node (ref "IO_UC") (pin "5") (pinfunction "(PCI19/INT1/OC2B)PD3_5") (pintype "bidirectional"))
      (node (ref "RO21") (pin "2") (pinfunction "2_2") (pintype "passive"))
      (node (ref "RO22") (pin "2") (pinfunction "2_2") (pintype "passive"))
    )
    (net (code "34") (name "/OUT3") (class "Default")
      (node (ref "IO_UC") (pin "6") (pinfunction "(PCI20/XCK/T0)PD4_6") (pintype "bidirectional"))
      (node (ref "RO31") (pin "2") (pinfunction "2_2") (pintype "passive"))
      (node (ref "RO32") (pin "2") (pinfunction "2_2") (pintype "passive"))
    )
    (net (code "35") (name "/OUT4") (class "Default")
      (node (ref "IO_UC") (pin "11") (pinfunction "(PCI21/T1/OC0B)PD5_11") (pintype "bidirectional"))
      (node (ref "RO41") (pin "2") (pinfunction "2_2") (pintype "passive"))
      (node (ref "RO42") (pin "2") (pinfunction "2_2") (pintype "passive"))
    )
    (net (code "36") (name "/OUT5") (class "Default")
      (node (ref "IO_UC") (pin "12") (pinfunction "(PCI22/AIN0OC0A)PD6_12") (pintype "bidirectional"))
      (node (ref "R51") (pin "2") (pinfunction "2_2") (pintype "passive"))
      (node (ref "RO52") (pin "2") (pinfunction "2_2") (pintype "passive"))
    )
    (net (code "37") (name "/OUT6") (class "Default")
      (node (ref "IO_UC") (pin "13") (pinfunction "(PCI23/AIN1)PD7_13") (pintype "bidirectional"))
      (node (ref "R61") (pin "2") (pinfunction "2_2") (pintype "passive"))
      (node (ref "RO62") (pin "2") (pinfunction "2_2") (pintype "passive"))
    )
    (net (code "38") (name "/OUT7") (class "Default")
      (node (ref "IO_UC") (pin "14") (pinfunction "(PCI0/ICP/CLKO)PB0_14") (pintype "bidirectional"))
      (node (ref "RO71") (pin "2") (pinfunction "2_2") (pintype "passive"))
      (node (ref "RO72") (pin "2") (pinfunction "2_2") (pintype "passive"))
    )
    (net (code "39") (name "/OUT8") (class "Default")
      (node (ref "IO_UC") (pin "15") (pinfunction "(PCI1/OC1A/OC1S)PB1_15") (pintype "bidirectional"))
      (node (ref "RO81") (pin "2") (pinfunction "2_2") (pintype "passive"))
      (node (ref "RO82") (pin "2") (pinfunction "2_2") (pintype "passive"))
    )
    (net (code "40") (name "/PRESS_SEN1") (class "Default")
      (node (ref "ASC") (pin "6") (pinfunction "-IN_6") (pintype "input"))
      (node (ref "ASC") (pin "7") (pinfunction "OUT_7") (pintype "output"))
      (node (ref "U$1") (pin "17") (pinfunction "17_17") (pintype "passive"))
      (node (ref "U$3") (pin "3") (pinfunction "SVP_3") (pintype "bidirectional"))
    )
    (net (code "41") (name "/PRESS_SEN2") (class "Default")
      (node (ref "ASC") (pin "1") (pinfunction "OUT_1") (pintype "output"))
      (node (ref "ASC") (pin "2") (pinfunction "-IN_2") (pintype "input"))
      (node (ref "U$1") (pin "16") (pinfunction "16_16") (pintype "passive"))
      (node (ref "U$3") (pin "4") (pinfunction "SVN_4") (pintype "bidirectional"))
    )
    (net (code "42") (name "/RTS") (class "Default")
      (node (ref "C_URTS") (pin "1") (pinfunction "1_1") (pintype "passive"))
      (node (ref "FTDI") (pin "6") (pinfunction "6_6") (pintype "passive"))
    )
    (net (code "43") (name "/SCK") (class "Default")
      (node (ref "U$14") (pin "11") (pinfunction "11_11") (pintype "passive"))
      (node (ref "U$15") (pin "SCK") (pinfunction "SCK_SCK") (pintype "bidirectional"))
      (node (ref "U$3") (pin "30") (pinfunction "IO18_30") (pintype "bidirectional"))
    )
    (net (code "44") (name "/SCL") (class "Default")
      (node (ref "I2CR1") (pin "1") (pinfunction "1_1") (pintype "passive"))
      (node (ref "I2C_BUS") (pin "1") (pinfunction "1_1") (pintype "passive"))
      (node (ref "OLED_DISPLAY") (pin "1") (pinfunction "1_1") (pintype "passive"))
      (node (ref "U$14") (pin "17") (pinfunction "17_17") (pintype "passive"))
      (node (ref "U$3") (pin "36") (pinfunction "IO22_36") (pintype "bidirectional"))
      (node (ref "U$6") (pin "SCL") (pinfunction "SCL_SCL") (pintype "bidirectional"))
    )
    (net (code "45") (name "/SDA") (class "Default")
      (node (ref "I2CR2") (pin "1") (pinfunction "1_1") (pintype "passive"))
      (node (ref "I2C_BUS") (pin "2") (pinfunction "2_2") (pintype "passive"))
      (node (ref "OLED_DISPLAY") (pin "2") (pinfunction "2_2") (pintype "passive"))
      (node (ref "U$14") (pin "14") (pinfunction "14_14") (pintype "passive"))
      (node (ref "U$3") (pin "33") (pinfunction "IO21_33") (pintype "bidirectional"))
      (node (ref "U$6") (pin "SDA") (pinfunction "SDA_SDA") (pintype "bidirectional"))
    )
    (net (code "46") (name "/SD_CS") (class "Default")
      (node (ref "U$14") (pin "10") (pinfunction "10_10") (pintype "passive"))
      (node (ref "U$15") (pin "CS") (pinfunction "CS_CS") (pintype "bidirectional"))
      (node (ref "U$3") (pin "29") (pinfunction "IO5_29") (pintype "bidirectional"))
    )
    (net (code "47") (name "/SPARE_IO0") (class "Default")
      (node (ref "U$14") (pin "6") (pinfunction "6_6") (pintype "passive"))
      (node (ref "U$3") (pin "25") (pinfunction "IO0_25") (pintype "bidirectional"))
    )
    (net (code "48") (name "/SPARE_IO1") (class "Default")
      (node (ref "U$14") (pin "16") (pinfunction "16_16") (pintype "passive"))
      (node (ref "U$3") (pin "35") (pinfunction "TXD0_35") (pintype "bidirectional"))
    )
    (net (code "49") (name "/SPARE_IO2") (class "Default")
      (node (ref "U$14") (pin "5") (pinfunction "5_5") (pintype "passive"))
      (node (ref "U$3") (pin "24") (pinfunction "IO2_24") (pintype "bidirectional"))
    )
    (net (code "50") (name "/SPARE_IO3") (class "Default")
      (node (ref "U$14") (pin "15") (pinfunction "15_15") (pintype "passive"))
      (node (ref "U$3") (pin "34") (pinfunction "RXD0_34") (pintype "bidirectional"))
    )
    (net (code "51") (name "/SPARE_IO6") (class "Default")
      (node (ref "U$14") (pin "1") (pinfunction "1_1") (pintype "passive"))
      (node (ref "U$3") (pin "20") (pinfunction "CLK_20") (pintype "bidirectional"))
    )
    (net (code "52") (name "/SPARE_IO7") (class "Default")
      (node (ref "U$14") (pin "2") (pinfunction "2_2") (pintype "passive"))
      (node (ref "U$3") (pin "21") (pinfunction "SD0_21") (pintype "bidirectional"))
    )
    (net (code "53") (name "/SPARE_IO8") (class "Default")
      (node (ref "U$14") (pin "3") (pinfunction "3_3") (pintype "passive"))
      (node (ref "U$3") (pin "22") (pinfunction "SD1_22") (pintype "bidirectional"))
    )
    (net (code "54") (name "/SPARE_IO9") (class "Default")
      (node (ref "U$1") (pin "4") (pinfunction "4_4") (pintype "passive"))
      (node (ref "U$3") (pin "16") (pinfunction "SD2_16") (pintype "bidirectional"))
    )
    (net (code "55") (name "/SPARE_IO10") (class "Default")
      (node (ref "U$1") (pin "3") (pinfunction "3_3") (pintype "passive"))
      (node (ref "U$3") (pin "17") (pinfunction "SD3_17") (pintype "bidirectional"))
    )
    (net (code "56") (name "/SPARE_IO11") (class "Default")
      (node (ref "U$1") (pin "2") (pinfunction "2_2") (pintype "passive"))
      (node (ref "U$3") (pin "18") (pinfunction "CMD_18") (pintype "bidirectional"))
    )
    (net (code "57") (name "/SPARE_IO12") (class "Default")
      (node (ref "U$1") (pin "7") (pinfunction "7_7") (pintype "passive"))
      (node (ref "U$3") (pin "13") (pinfunction "IO12_13") (pintype "bidirectional"))
    )
    (net (code "58") (name "/SPARE_IO13") (class "Default")
      (node (ref "U$1") (pin "5") (pinfunction "5_5") (pintype "passive"))
      (node (ref "U$3") (pin "15") (pinfunction "IO13_15") (pintype "bidirectional"))
    )
    (net (code "59") (name "/SPARE_IO14") (class "Default")
      (node (ref "U$1") (pin "8") (pinfunction "8_8") (pintype "passive"))
      (node (ref "U$3") (pin "12") (pinfunction "IO14_12") (pintype "bidirectional"))
    )
    (net (code "60") (name "/SPARE_IO15") (class "Default")
      (node (ref "U$14") (pin "4") (pinfunction "4_4") (pintype "passive"))
      (node (ref "U$3") (pin "23") (pinfunction "IO15_23") (pintype "bidirectional"))
    )
    (net (code "61") (name "/SPARE_IO34") (class "Default")
      (node (ref "U$1") (pin "15") (pinfunction "15_15") (pintype "passive"))
      (node (ref "U$3") (pin "5") (pinfunction "IO34_5") (pintype "bidirectional"))
    )
    (net (code "62") (name "/SPARE_IO35") (class "Default")
      (node (ref "U$1") (pin "14") (pinfunction "14_14") (pintype "passive"))
      (node (ref "U$3") (pin "6") (pinfunction "IO35_6") (pintype "bidirectional"))
    )
    (net (code "63") (name "/STAY_ALIVE1") (class "Default")
      (node (ref "SAD1") (pin "A") (pinfunction "A_A") (pintype "passive"))
      (node (ref "U$1") (pin "13") (pinfunction "13_13") (pintype "passive"))
      (node (ref "U$3") (pin "7") (pinfunction "IO32_7") (pintype "bidirectional"))
    )
    (net (code "64") (name "/STAY_ALIVE2") (class "Default")
      (node (ref "SAD2") (pin "A") (pinfunction "A_A") (pintype "passive"))
      (node (ref "U$1") (pin "12") (pinfunction "12_12") (pintype "passive"))
      (node (ref "U$3") (pin "8") (pinfunction "IO33_8") (pintype "bidirectional"))
    )
    (net (code "65") (name "/TEMP_SEN") (class "Default")
      (node (ref "R_TEMP") (pin "1") (pinfunction "1_1") (pintype "passive"))
      (node (ref "TEMP_SENSOR") (pin "2") (pinfunction "2_2") (pintype "passive"))
      (node (ref "U$1") (pin "10") (pinfunction "10_10") (pintype "passive"))
      (node (ref "U$3") (pin "10") (pinfunction "IO26_10") (pintype "bidirectional"))
    )
    (net (code "66") (name "/U_RESET") (class "Default")
      (node (ref "C_URTS") (pin "2") (pinfunction "2_2") (pintype "passive"))
      (node (ref "D_URES") (pin "A") (pinfunction "A_A") (pintype "passive"))
      (node (ref "IO_UC") (pin "1") (pinfunction "PC6(/RESET/PCI14)_1") (pintype "bidirectional"))
      (node (ref "R_URES") (pin "2") (pinfunction "2_2") (pintype "passive"))
      (node (ref "U_RESET") (pin "3") (pinfunction "3_3") (pintype "passive"))
      (node (ref "U_RESET") (pin "4") (pinfunction "4_4") (pintype "passive"))
    )
    (net (code "67") (name "/U_RX") (class "Default")
      (node (ref "FTDI") (pin "4") (pinfunction "4_4") (pintype "passive"))
      (node (ref "IO_UC") (pin "2") (pinfunction "(PCI16/RXD)PD0_2") (pintype "bidirectional"))
      (node (ref "LS12") (pin "1") (pinfunction "1_1") (pintype "passive"))
      (node (ref "LSQ1") (pin "3") (pinfunction "D_3") (pintype "bidirectional"))
    )
    (net (code "68") (name "/U_SPARE") (class "Default")
      (node (ref "IO_UC") (pin "16") (pinfunction "(PCI2/SS/OC1B)PB2_16") (pintype "bidirectional"))
    )
    (net (code "69") (name "/U_TX") (class "Default")
      (node (ref "IO_UC") (pin "3") (pinfunction "(PCI17/TXD)PD1_3") (pintype "bidirectional"))
      (node (ref "LS22") (pin "1") (pinfunction "1_1") (pintype "passive"))
      (node (ref "LSQ2") (pin "3") (pinfunction "D_3") (pintype "bidirectional"))
      (node (ref "RDX") (pin "2") (pinfunction "2_2") (pintype "passive"))
    )
    (net (code "70") (name "GND") (class "Default")
      (node (ref "2N2222_1") (pin "E") (pinfunction "E_E") (pintype "passive"))
      (node (ref "2N2222_2") (pin "E") (pinfunction "E_E") (pintype "passive"))
      (node (ref "2N2222_3") (pin "E") (pinfunction "E_E") (pintype "passive"))
      (node (ref "2N2222_4") (pin "E") (pinfunction "E_E") (pintype "passive"))
      (node (ref "2N2222_5") (pin "E") (pinfunction "E_E") (pintype "passive"))
      (node (ref "2N2222_6") (pin "E") (pinfunction "E_E") (pintype "passive"))
      (node (ref "2N2222_7") (pin "E") (pinfunction "E_E") (pintype "passive"))
      (node (ref "2N2222_8") (pin "E") (pinfunction "E_E") (pintype "passive"))
      (node (ref "ASC") (pin "4") (pinfunction "P$V-_4") (pintype "bidirectional"))
      (node (ref "CP01") (pin "-") (pinfunction "-_-") (pintype "passive"))
      (node (ref "CP31") (pin "-") (pinfunction "-_-") (pintype "passive"))
      (node (ref "CP51") (pin "-") (pinfunction "-_-") (pintype "passive"))
      (node (ref "C_BT") (pin "2") (pinfunction "2_2") (pintype "passive"))
      (node (ref "C_FM") (pin "2") (pinfunction "2_2") (pintype "passive"))
      (node (ref "C_RTC") (pin "1") (pinfunction "1_1") (pintype "passive"))
      (node (ref "C_RTC1") (pin "2") (pinfunction "2_2") (pintype "passive"))
      (node (ref "C_U") (pin "1") (pinfunction "1_1") (pintype "passive"))
      (node (ref "C_USD") (pin "2") (pinfunction "2_2") (pintype "passive"))
      (node (ref "C_UXTAL1") (pin "2") (pinfunction "2_2") (pintype "passive"))
      (node (ref "C_UXTAL2") (pin "2") (pinfunction "2_2") (pintype "passive"))
      (node (ref "FTDI") (pin "1") (pinfunction "1_1") (pintype "passive"))
      (node (ref "FTDI") (pin "2") (pinfunction "2_2") (pintype "passive"))
      (node (ref "I2C_BUS") (pin "4") (pinfunction "4_4") (pintype "passive"))
      (node (ref "IO_UC") (pin "22") (pinfunction "AGND_22") (pintype "bidirectional"))
      (node (ref "IO_UC") (pin "8") (pinfunction "GND_8") (pintype "bidirectional"))
      (node (ref "OLED_DISPLAY") (pin "4") (pinfunction "4_4") (pintype "passive"))
      (node (ref "PR_3.3V") (pin "1") (pinfunction "1_1") (pintype "passive"))
      (node (ref "PR_5V") (pin "1") (pinfunction "1_1") (pintype "passive"))
      (node (ref "PSU") (pin "2") (pinfunction "KL_2") (pintype "passive"))
      (node (ref "R51") (pin "1") (pinfunction "1_1") (pintype "passive"))
      (node (ref "R61") (pin "1") (pinfunction "1_1") (pintype "passive"))
      (node (ref "REG_3V3") (pin "1") (pinfunction "GND_1") (pintype "input"))
      (node (ref "REG_5V") (pin "1") (pinfunction "GND_1") (pintype "input"))
      (node (ref "RI1") (pin "2") (pinfunction "2_2") (pintype "passive"))
      (node (ref "RI2") (pin "2") (pinfunction "2_2") (pintype "passive"))
      (node (ref "RI3") (pin "2") (pinfunction "2_2") (pintype "passive"))
      (node (ref "RI4") (pin "2") (pinfunction "2_2") (pintype "passive"))
      (node (ref "RI5") (pin "2") (pinfunction "2_2") (pintype "passive"))
      (node (ref "RI6") (pin "2") (pinfunction "2_2") (pintype "passive"))
      (node (ref "RI7") (pin "2") (pinfunction "2_2") (pintype "passive"))
      (node (ref "RI8") (pin "2") (pinfunction "2_2") (pintype "passive"))
      (node (ref "RO11") (pin "1") (pinfunction "1_1") (pintype "passive"))
      (node (ref "RO21") (pin "1") (pinfunction "1_1") (pintype "passive"))
      (node (ref "RO31") (pin "1") (pinfunction "1_1") (pintype "passive"))
      (node (ref "RO41") (pin "1") (pinfunction "1_1") (pintype "passive"))
      (node (ref "RO71") (pin "1") (pinfunction "1_1") (pintype "passive"))
      (node (ref "RO81") (pin "1") (pinfunction "1_1") (pintype "passive"))
      (node (ref "R_AUTO") (pin "1") (pinfunction "1_1") (pintype "passive"))
      (node (ref "SA1") (pin "1") (pinfunction "1_1") (pintype "passive"))
      (node (ref "SA2") (pin "1") (pinfunction "1_1") (pintype "passive"))
      (node (ref "SC12") (pin "1") (pinfunction "1_1") (pintype "passive"))
      (node (ref "SC22") (pin "1") (pinfunction "1_1") (pintype "passive"))
      (node (ref "SV2") (pin "1") (pinfunction "1_1") (pintype "passive"))
      (node (ref "SV3") (pin "1") (pinfunction "1_1") (pintype "passive"))
      (node (ref "TEMP_SENSOR") (pin "1") (pinfunction "1_1") (pintype "passive"))
      (node (ref "U$1") (pin "6") (pinfunction "6_6") (pintype "passive"))
      (node (ref "U$14") (pin "13") (pinfunction "13_13") (pintype "passive"))
      (node (ref "U$14") (pin "19") (pinfunction "19_19") (pintype "passive"))
      (node (ref "U$15") (pin "GND") (pinfunction "GND_GND") (pintype "bidirectional"))
      (node (ref "U$2") (pin "GND") (pinfunction "GND_GND") (pintype "bidirectional"))
      (node (ref "U$3") (pin "14") (pinfunction "GND_14") (pintype "bidirectional"))
      (node (ref "U$3") (pin "32") (pinfunction "GND_32") (pintype "bidirectional"))
      (node (ref "U$3") (pin "38") (pinfunction "GND_38") (pintype "bidirectional"))
      (node (ref "U$6") (pin "GND") (pinfunction "GND_GND") (pintype "bidirectional"))
      (node (ref "U_RESET") (pin "1") (pinfunction "1_1") (pintype "passive"))
      (node (ref "U_RESET") (pin "2") (pinfunction "2_2") (pintype "passive"))
    )
    (net (code "71") (name "Net-(2N2222_1-PadB)") (class "Default")
      (node (ref "2N2222_1") (pin "B") (pinfunction "B_B") (pintype "passive"))
      (node (ref "RO12") (pin "1") (pinfunction "1_1") (pintype "passive"))
    )
    (net (code "72") (name "Net-(2N2222_2-PadB)") (class "Default")
      (node (ref "2N2222_2") (pin "B") (pinfunction "B_B") (pintype "passive"))
      (node (ref "RO22") (pin "1") (pinfunction "1_1") (pintype "passive"))
    )
    (net (code "73") (name "Net-(2N2222_3-PadB)") (class "Default")
      (node (ref "2N2222_3") (pin "B") (pinfunction "B_B") (pintype "passive"))
      (node (ref "RO32") (pin "1") (pinfunction "1_1") (pintype "passive"))
    )
    (net (code "74") (name "Net-(2N2222_4-PadB)") (class "Default")
      (node (ref "2N2222_4") (pin "B") (pinfunction "B_B") (pintype "passive"))
      (node (ref "RO42") (pin "1") (pinfunction "1_1") (pintype "passive"))
    )
    (net (code "75") (name "Net-(2N2222_5-PadB)") (class "Default")
      (node (ref "2N2222_5") (pin "B") (pinfunction "B_B") (pintype "passive"))
      (node (ref "RO52") (pin "1") (pinfunction "1_1") (pintype "passive"))
    )
    (net (code "76") (name "Net-(2N2222_6-PadB)") (class "Default")
      (node (ref "2N2222_6") (pin "B") (pinfunction "B_B") (pintype "passive"))
      (node (ref "RO62") (pin "1") (pinfunction "1_1") (pintype "passive"))
    )
    (net (code "77") (name "Net-(2N2222_7-PadB)") (class "Default")
      (node (ref "2N2222_7") (pin "B") (pinfunction "B_B") (pintype "passive"))
      (node (ref "RO72") (pin "1") (pinfunction "1_1") (pintype "passive"))
    )
    (net (code "78") (name "Net-(2N2222_8-PadB)") (class "Default")
      (node (ref "2N2222_8") (pin "B") (pinfunction "B_B") (pintype "passive"))
      (node (ref "RO82") (pin "1") (pinfunction "1_1") (pintype "passive"))
    )
    (net (code "79") (name "Net-(ASCA-+IN)") (class "Default")
      (node (ref "ASC") (pin "3") (pinfunction "+IN_3") (pintype "input"))
      (node (ref "SC21") (pin "1") (pinfunction "1_1") (pintype "passive"))
      (node (ref "SC22") (pin "2") (pinfunction "2_2") (pintype "passive"))
    )
    (net (code "80") (name "Net-(ASCB-+IN)") (class "Default")
      (node (ref "ASC") (pin "5") (pinfunction "+IN_5") (pintype "input"))
      (node (ref "SC11") (pin "1") (pinfunction "1_1") (pintype "passive"))
      (node (ref "SC12") (pin "2") (pinfunction "2_2") (pintype "passive"))
    )
    (net (code "81") (name "Net-(D_3V3-C)") (class "Default")
      (node (ref "D_3V3") (pin "K") (pinfunction "C_K") (pintype "passive"))
      (node (ref "PR_3.3V") (pin "2") (pinfunction "2_2") (pintype "passive"))
    )
    (net (code "82") (name "Net-(D_5V-C)") (class "Default")
      (node (ref "D_5V") (pin "K") (pinfunction "C_K") (pintype "passive"))
      (node (ref "PR_5V") (pin "2") (pinfunction "2_2") (pintype "passive"))
    )
    (net (code "83") (name "Net-(FTDI-Pad5)") (class "Default")
      (node (ref "FTDI") (pin "5") (pinfunction "5_5") (pintype "passive"))
      (node (ref "RDX") (pin "1") (pinfunction "1_1") (pintype "passive"))
    )
    (net (code "84") (name "Net-(IO_UC-PB6(XTAL1{slash}TOSC1{slash}PCI6))") (class "Default")
      (node (ref "C_UXTAL1") (pin "1") (pinfunction "1_1") (pintype "passive"))
      (node (ref "IO_UC") (pin "9") (pinfunction "PB6(XTAL1/TOSC1/PCI6)_9") (pintype "bidirectional"))
      (node (ref "XTALU") (pin "2") (pinfunction "2_2") (pintype "passive"))
    )
    (net (code "85") (name "Net-(IO_UC-PB7(XTAL2{slash}TOSC2{slash}PCI7))") (class "Default")
      (node (ref "C_UXTAL2") (pin "1") (pinfunction "1_1") (pintype "passive"))
      (node (ref "IO_UC") (pin "10") (pinfunction "PB7(XTAL2/TOSC2/PCI7)_10") (pintype "bidirectional"))
      (node (ref "XTALU") (pin "1") (pinfunction "1_1") (pintype "passive"))
    )
    (net (code "86") (name "Net-(LO1-C)") (class "Default")
      (node (ref "2N2222_1") (pin "C") (pinfunction "C_C") (pintype "passive"))
      (node (ref "LO1") (pin "K") (pinfunction "C_K") (pintype "passive"))
      (node (ref "U$4") (pin "4") (pinfunction "-_4") (pintype "bidirectional"))
    )
    (net (code "87") (name "Net-(LO1-PadA)") (class "Default")
      (node (ref "LO1") (pin "A") (pinfunction "A_A") (pintype "passive"))
      (node (ref "RO13") (pin "1") (pinfunction "1_1") (pintype "passive"))
    )
    (net (code "88") (name "Net-(LO2-C)") (class "Default")
      (node (ref "2N2222_2") (pin "C") (pinfunction "C_C") (pintype "passive"))
      (node (ref "LO2") (pin "K") (pinfunction "C_K") (pintype "passive"))
      (node (ref "U$8") (pin "4") (pinfunction "-_4") (pintype "bidirectional"))
    )
    (net (code "89") (name "Net-(LO2-PadA)") (class "Default")
      (node (ref "LO2") (pin "A") (pinfunction "A_A") (pintype "passive"))
      (node (ref "RO23") (pin "1") (pinfunction "1_1") (pintype "passive"))
    )
    (net (code "90") (name "Net-(LO3-C)") (class "Default")
      (node (ref "2N2222_3") (pin "C") (pinfunction "C_C") (pintype "passive"))
      (node (ref "LO3") (pin "K") (pinfunction "C_K") (pintype "passive"))
      (node (ref "U$5") (pin "4") (pinfunction "-_4") (pintype "bidirectional"))
    )
    (net (code "91") (name "Net-(LO3-PadA)") (class "Default")
      (node (ref "LO3") (pin "A") (pinfunction "A_A") (pintype "passive"))
      (node (ref "RO33") (pin "1") (pinfunction "1_1") (pintype "passive"))
    )
    (net (code "92") (name "Net-(LO4-C)") (class "Default")
      (node (ref "2N2222_4") (pin "C") (pinfunction "C_C") (pintype "passive"))
      (node (ref "LO4") (pin "K") (pinfunction "C_K") (pintype "passive"))
      (node (ref "U$10") (pin "4") (pinfunction "-_4") (pintype "bidirectional"))
    )
    (net (code "93") (name "Net-(LO4-PadA)") (class "Default")
      (node (ref "LO4") (pin "A") (pinfunction "A_A") (pintype "passive"))
      (node (ref "RO43") (pin "1") (pinfunction "1_1") (pintype "passive"))
    )
    (net (code "94") (name "Net-(LO5-C)") (class "Default")
      (node (ref "2N2222_5") (pin "C") (pinfunction "C_C") (pintype "passive"))
      (node (ref "LO5") (pin "K") (pinfunction "C_K") (pintype "passive"))
      (node (ref "U$9") (pin "4") (pinfunction "-_4") (pintype "bidirectional"))
    )
    (net (code "95") (name "Net-(LO5-PadA)") (class "Default")
      (node (ref "LO5") (pin "A") (pinfunction "A_A") (pintype "passive"))
      (node (ref "RO53") (pin "1") (pinfunction "1_1") (pintype "passive"))
    )
    (net (code "96") (name "Net-(LO6-C)") (class "Default")
      (node (ref "2N2222_6") (pin "C") (pinfunction "C_C") (pintype "passive"))
      (node (ref "LO6") (pin "K") (pinfunction "C_K") (pintype "passive"))
      (node (ref "U$11") (pin "4") (pinfunction "-_4") (pintype "bidirectional"))
    )
    (net (code "97") (name "Net-(LO6-PadA)") (class "Default")
      (node (ref "LO6") (pin "A") (pinfunction "A_A") (pintype "passive"))
      (node (ref "RO63") (pin "1") (pinfunction "1_1") (pintype "passive"))
    )
    (net (code "98") (name "Net-(LO7-C)") (class "Default")
      (node (ref "2N2222_7") (pin "C") (pinfunction "C_C") (pintype "passive"))
      (node (ref "LO7") (pin "K") (pinfunction "C_K") (pintype "passive"))
      (node (ref "U$12") (pin "4") (pinfunction "-_4") (pintype "bidirectional"))
    )
    (net (code "99") (name "Net-(LO7-PadA)") (class "Default")
      (node (ref "LO7") (pin "A") (pinfunction "A_A") (pintype "passive"))
      (node (ref "RO73") (pin "1") (pinfunction "1_1") (pintype "passive"))
    )
    (net (code "100") (name "Net-(LO8-C)") (class "Default")
      (node (ref "2N2222_8") (pin "C") (pinfunction "C_C") (pintype "passive"))
      (node (ref "LO8") (pin "K") (pinfunction "C_K") (pintype "passive"))
      (node (ref "U$13") (pin "4") (pinfunction "-_4") (pintype "bidirectional"))
    )
    (net (code "101") (name "Net-(LO8-PadA)") (class "Default")
      (node (ref "LO8") (pin "A") (pinfunction "A_A") (pintype "passive"))
      (node (ref "RO83") (pin "1") (pinfunction "1_1") (pintype "passive"))
    )
    (net (code "102") (name "Net-(PSUA-KL)") (class "Default")
      (node (ref "D_PSU") (pin "A") (pinfunction "A_A") (pintype "passive"))
      (node (ref "PSU") (pin "1") (pinfunction "KL_1") (pintype "passive"))
    )
    (net (code "103") (name "Net-(REG_3V3-IN)") (class "Default")
      (node (ref "CP01") (pin "+") (pinfunction "+_+") (pintype "passive"))
      (node (ref "D_PSU") (pin "C") (pinfunction "C_C") (pintype "passive"))
      (node (ref "D_PSU1") (pin "C") (pinfunction "C_C") (pintype "passive"))
      (node (ref "D_PSU2") (pin "C") (pinfunction "C_C") (pintype "passive"))
      (node (ref "REG_3V3") (pin "3") (pinfunction "IN_3") (pintype "input"))
      (node (ref "REG_5V") (pin "3") (pinfunction "IN_3") (pintype "input"))
    )
    (net (code "104") (name "Net-(SAD1-C)") (class "Default")
      (node (ref "SA1") (pin "2") (pinfunction "2_2") (pintype "passive"))
      (node (ref "SAD1") (pin "K") (pinfunction "C_K") (pintype "passive"))
    )
    (net (code "105") (name "Net-(SAD2-C)") (class "Default")
      (node (ref "SA2") (pin "2") (pinfunction "2_2") (pintype "passive"))
      (node (ref "SAD2") (pin "K") (pinfunction "C_K") (pintype "passive"))
    )
    (net (code "106") (name "Net-(SC11-Pad2)") (class "Default")
      (node (ref "SC11") (pin "2") (pinfunction "2_2") (pintype "passive"))
      (node (ref "SV3") (pin "3") (pinfunction "3_3") (pintype "passive"))
    )
    (net (code "107") (name "Net-(SC21-Pad2)") (class "Default")
      (node (ref "SC21") (pin "2") (pinfunction "2_2") (pintype "passive"))
      (node (ref "SV2") (pin "3") (pinfunction "3_3") (pintype "passive"))
    )
    (net (code "108") (name "Net-(U$4-L2)") (class "Default")
      (node (ref "FUSE1") (pin "1") (pinfunction "1_1") (pintype "passive"))
      (node (ref "U$4") (pin "2") (pinfunction "L2_2") (pintype "bidirectional"))
    )
    (net (code "109") (name "Net-(U$5-L2)") (class "Default")
      (node (ref "FUSE3") (pin "1") (pinfunction "1_1") (pintype "passive"))
      (node (ref "U$5") (pin "2") (pinfunction "L2_2") (pintype "bidirectional"))
    )
    (net (code "110") (name "Net-(U$8-L2)") (class "Default")
      (node (ref "FUSE2") (pin "1") (pinfunction "1_1") (pintype "passive"))
      (node (ref "U$8") (pin "2") (pinfunction "L2_2") (pintype "bidirectional"))
    )
    (net (code "111") (name "Net-(U$9-L2)") (class "Default")
      (node (ref "FUSE5") (pin "1") (pinfunction "1_1") (pintype "passive"))
      (node (ref "U$9") (pin "2") (pinfunction "L2_2") (pintype "bidirectional"))
    )
    (net (code "112") (name "Net-(U$10-L2)") (class "Default")
      (node (ref "FUSE4") (pin "1") (pinfunction "1_1") (pintype "passive"))
      (node (ref "U$10") (pin "2") (pinfunction "L2_2") (pintype "bidirectional"))
    )
    (net (code "113") (name "Net-(U$11-L2)") (class "Default")
      (node (ref "FUSE6") (pin "1") (pinfunction "1_1") (pintype "passive"))
      (node (ref "U$11") (pin "2") (pinfunction "L2_2") (pintype "bidirectional"))
    )
    (net (code "114") (name "Net-(U$12-L2)") (class "Default")
      (node (ref "FUSE7") (pin "1") (pinfunction "1_1") (pintype "passive"))
      (node (ref "U$12") (pin "2") (pinfunction "L2_2") (pintype "bidirectional"))
    )
    (net (code "115") (name "Net-(U$13-L2)") (class "Default")
      (node (ref "FUSE8") (pin "1") (pinfunction "1_1") (pintype "passive"))
      (node (ref "U$13") (pin "2") (pinfunction "L2_2") (pintype "bidirectional"))
    )
    (net (code "116") (name "unconnected-(U$2-Pad5V)") (class "Default")
      (node (ref "U$2") (pin "5V") (pinfunction "5V_5V") (pintype "bidirectional"))
    )
    (net (code "117") (name "unconnected-(U$2-PadKEY)") (class "Default")
      (node (ref "U$2") (pin "KEY") (pinfunction "KEY_KEY") (pintype "bidirectional"))
    )
    (net (code "118") (name "unconnected-(U$6-Pad32K)") (class "Default")
      (node (ref "U$6") (pin "32K") (pinfunction "32K_32K") (pintype "bidirectional"))
    )
    (net (code "119") (name "unconnected-(U$6-PadBAT)") (class "Default")
      (node (ref "U$6") (pin "BAT") (pinfunction "BAT_BAT") (pintype "bidirectional"))
    )
    (net (code "120") (name "unconnected-(U$6-PadRST)") (class "Default")
      (node (ref "U$6") (pin "RST") (pinfunction "RST_RST") (pintype "bidirectional"))
    )
    (net (code "121") (name "unconnected-(U$6-PadSQW)") (class "Default")
      (node (ref "U$6") (pin "SQW") (pinfunction "SQW_SQW") (pintype "bidirectional"))
    )
  )
)
